# dosimeter.net
KiCad netlist of a schematic drawn in EAGLE
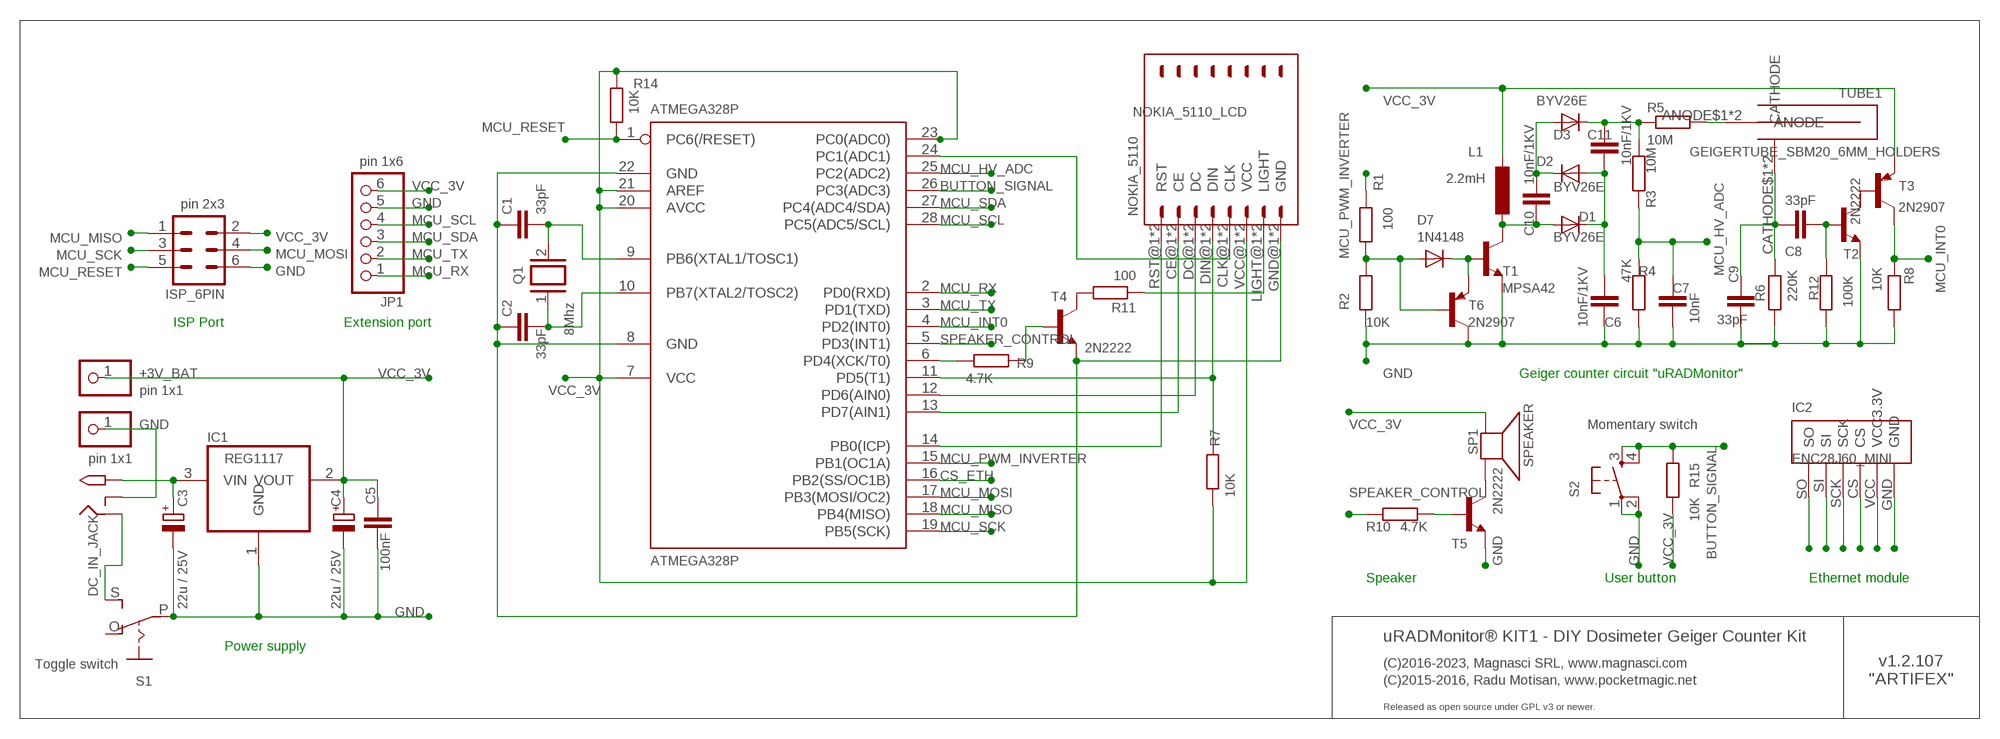
[diagram p0: schematic, sheet 1]

(export (version "E")
  (design (tool "Eeschema 10.0.6"))
  (components
    (comp (ref "+3V_BAT")
      (value "pin 1x1")
      (footprint "eagle-import:1X01")
      (libsource (lib "eagle-import") (part "PINHD-1X1"))
    )
    (comp (ref "ATMEGA328P")
      (value "ATMEGA328P")
      (footprint "eagle-import:DIL28-3")
      (libsource (lib "eagle-import") (part "MEGA8-P"))
    )
    (comp (ref "C1")
      (value "33pF")
      (footprint "eagle-import:C2.5-2")
      (libsource (lib "eagle-import") (part "C2.5/2"))
    )
    (comp (ref "C2")
      (value "33pF")
      (footprint "eagle-import:C2.5-2")
      (libsource (lib "eagle-import") (part "C2.5/2"))
    )
    (comp (ref "C3")
      (value "22u / 25V")
      (footprint "eagle-import:TT2D4L")
      (libsource (lib "eagle-import") (part "CPOL-EUTT2D4L"))
    )
    (comp (ref "C4")
      (value "22u / 25V")
      (footprint "eagle-import:TT2D4L")
      (libsource (lib "eagle-import") (part "CPOL-EUTT2D4L"))
    )
    (comp (ref "C5")
      (value "100nF")
      (footprint "eagle-import:C2.5-2")
      (libsource (lib "eagle-import") (part "C2.5/2"))
    )
    (comp (ref "C6")
      (value "10nF/1KV")
      (footprint "eagle-import:C5B3")
      (libsource (lib "eagle-import") (part "C5/3"))
    )
    (comp (ref "C7")
      (value "10nF")
      (footprint "eagle-import:C2.5-2")
      (libsource (lib "eagle-import") (part "C2.5/2"))
    )
    (comp (ref "C8")
      (value "33pF")
      (footprint "eagle-import:C2.5-2")
      (libsource (lib "eagle-import") (part "C2.5/2"))
    )
    (comp (ref "C9")
      (value "33pF")
      (footprint "eagle-import:C2.5-2")
      (libsource (lib "eagle-import") (part "C2.5/2"))
    )
    (comp (ref "C10")
      (value "10nF/1KV")
      (footprint "eagle-import:C5B3")
      (libsource (lib "eagle-import") (part "C5/3"))
    )
    (comp (ref "C11")
      (value "10nF/1KV")
      (footprint "eagle-import:C5B3")
      (libsource (lib "eagle-import") (part "C5/3"))
    )
    (comp (ref "D1")
      (value "BYV26E")
      (footprint "eagle-import:DO41-7.6")
      (libsource (lib "eagle-import") (part "DIODE-DO41-7.6"))
    )
    (comp (ref "D2")
      (value "BYV26E")
      (footprint "eagle-import:DO41-7.6")
      (libsource (lib "eagle-import") (part "DIODE-DO41-7.6"))
    )
    (comp (ref "D3")
      (value "BYV26E")
      (footprint "eagle-import:DO41-7.6")
      (libsource (lib "eagle-import") (part "DIODE-DO41-7.6"))
    )
    (comp (ref "D7")
      (value "1N4148")
      (footprint "eagle-import:D-5")
      (libsource (lib "eagle-import") (part "DIODE-D-5"))
    )
    (comp (ref "DC_IN_JACK")
      (value "DC IN JACK")
      (footprint "eagle-import:PJ-102A")
      (libsource (lib "eagle-import") (part "2.1MMJACKTHM"))
    )
    (comp (ref "GND")
      (value "pin 1x1")
      (footprint "eagle-import:1X01")
      (libsource (lib "eagle-import") (part "PINHD-1X1"))
    )
    (comp (ref "IC1")
      (value "REG1117")
      (footprint "eagle-import:SOT223")
      (libsource (lib "eagle-import") (part "REG1117"))
    )
    (comp (ref "IC2")
      (value "ENC28J60_MINI")
      (footprint "eagle-import:ENC28J60_MINI")
      (libsource (lib "eagle-import") (part "ENC28J60_MINI"))
    )
    (comp (ref "ISP_6PIN")
      (value "pin 2x3")
      (footprint "eagle-import:MA03-2")
      (libsource (lib "eagle-import") (part "MA03-2"))
    )
    (comp (ref "JP1")
      (value "pin 1x6")
      (footprint "eagle-import:1X06-CLEAN")
      (libsource (lib "eagle-import") (part "PINHD-1X6CLEAN"))
    )
    (comp (ref "L1")
      (value "2.2mH")
      (footprint "eagle-import:0207_10")
      (libsource (lib "eagle-import") (part "L-EU0207/10"))
    )
    (comp (ref "NOKIA_5110")
      (value "NOKIA_5110_LCD")
      (footprint "eagle-import:NOKIA5110")
      (libsource (lib "eagle-import") (part "NOKIA5110"))
    )
    (comp (ref "Q1")
      (value "8Mhz")
      (footprint "eagle-import:QS")
      (libsource (lib "eagle-import") (part "XTAL/S"))
    )
    (comp (ref "R1")
      (value "100")
      (footprint "eagle-import:0204_7")
      (libsource (lib "eagle-import") (part "R-EU_0204/7"))
    )
    (comp (ref "R2")
      (value "10K")
      (footprint "eagle-import:0204_7")
      (libsource (lib "eagle-import") (part "R-EU_0204/7"))
    )
    (comp (ref "R3")
      (value "10M")
      (footprint "eagle-import:0204_7")
      (libsource (lib "eagle-import") (part "R-EU_0204/7"))
    )
    (comp (ref "R4")
      (value "47K")
      (footprint "eagle-import:0204_7")
      (libsource (lib "eagle-import") (part "R-EU_0204/7"))
    )
    (comp (ref "R5")
      (value "10M")
      (footprint "eagle-import:0204_7")
      (libsource (lib "eagle-import") (part "R-EU_0204/7"))
    )
    (comp (ref "R6")
      (value "220K")
      (footprint "eagle-import:0204_7")
      (libsource (lib "eagle-import") (part "R-EU_0204/7"))
    )
    (comp (ref "R7")
      (value "10K")
      (footprint "eagle-import:0204_7")
      (libsource (lib "eagle-import") (part "R-EU_0204/7"))
    )
    (comp (ref "R8")
      (value "10K")
      (footprint "eagle-import:0204_7")
      (libsource (lib "eagle-import") (part "R-EU_0204/7"))
    )
    (comp (ref "R9")
      (value "4.7K")
      (footprint "eagle-import:0204_7")
      (libsource (lib "eagle-import") (part "R-EU_0204/7"))
    )
    (comp (ref "R10")
      (value "4.7K")
      (footprint "eagle-import:0204_7")
      (libsource (lib "eagle-import") (part "R-EU_0204/7"))
    )
    (comp (ref "R11")
      (value "100")
      (footprint "eagle-import:0204_7")
      (libsource (lib "eagle-import") (part "R-EU_0204/7"))
    )
    (comp (ref "R12")
      (value "100K")
      (footprint "eagle-import:0204_7")
      (libsource (lib "eagle-import") (part "R-EU_0204/7"))
    )
    (comp (ref "R14")
      (value "10K")
      (footprint "eagle-import:0204_7")
      (libsource (lib "eagle-import") (part "R-EU_0204/7"))
    )
    (comp (ref "R15")
      (value "10K")
      (footprint "eagle-import:0204_7")
      (libsource (lib "eagle-import") (part "R-EU_0204/7"))
    )
    (comp (ref "S1")
      (value "Toggle switch")
      (footprint "eagle-import:EG1218")
      (libsource (lib "eagle-import") (part "EG1218S"))
    )
    (comp (ref "S2")
      (value "Momentary switch")
      (footprint "eagle-import:TACTILE-PTH")
      (libsource (lib "eagle-import") (part "TAC_SWITCHPTH"))
    )
    (comp (ref "SP1")
      (value "SPEAKER")
      (footprint "eagle-import:AL60P")
      (libsource (lib "eagle-import") (part "SPEAKER/AL60P"))
    )
    (comp (ref "T1")
      (value "MPSA42")
      (footprint "eagle-import:TO92-EBC-OVAL")
      (libsource (lib "eagle-import") (part "2N2222"))
    )
    (comp (ref "T2")
      (value "2N2222")
      (footprint "eagle-import:TO92-EBC")
      (libsource (lib "eagle-import") (part "-NPN-TO92-EBC2N2222"))
    )
    (comp (ref "T3")
      (value "2N2907")
      (footprint "eagle-import:TO92-EBC-OVAL")
      (libsource (lib "eagle-import") (part "2N2907"))
    )
    (comp (ref "T4")
      (value "2N2222")
      (footprint "eagle-import:TO92-EBC")
      (libsource (lib "eagle-import") (part "-NPN-TO92-EBC2N2222"))
    )
    (comp (ref "T5")
      (value "2N2222")
      (footprint "eagle-import:TO92-EBC")
      (libsource (lib "eagle-import") (part "-NPN-TO92-EBC2N2222"))
    )
    (comp (ref "T6")
      (value "2N2907")
      (footprint "eagle-import:TO92-EBC-OVAL")
      (libsource (lib "eagle-import") (part "2N2907"))
    )
    (comp (ref "TUBE1")
      (value "GEIGERTUBE_SBM20_6MM_HOLDERS")
      (footprint "eagle-import:GEIGERTUBE_SBM20_6MM_HOLDERS")
      (libsource (lib "eagle-import") (part "GEIGERTUBE_SBM20_6MM_HOLDERS"))
    )
  )
  (nets
    (net (code "1") (name "BUTTON_SIGNAL") (class "Default")
      (node (ref "ATMEGA328P") (pin "26") (pinfunction "PC3(ADC3)_26") (pintype "bidirectional"))
      (node (ref "R15") (pin "1") (pinfunction "1_1") (pintype "passive"))
      (node (ref "S2") (pin "3") (pinfunction "3_3") (pintype "passive"))
      (node (ref "S2") (pin "4") (pinfunction "4_4") (pintype "passive"))
    )
    (net (code "2") (name "CS_ETH") (class "Default")
      (node (ref "ATMEGA328P") (pin "16") (pinfunction "PB2(SS/OC1B)_16") (pintype "bidirectional"))
      (node (ref "IC2") (pin "CS") (pinfunction "CS_CS") (pintype "bidirectional"))
    )
    (net (code "3") (name "GND") (class "Default")
      (node (ref "ATMEGA328P") (pin "22") (pinfunction "GND_22") (pintype "power_in"))
      (node (ref "ATMEGA328P") (pin "8") (pinfunction "GND_8") (pintype "power_in"))
      (node (ref "C1") (pin "1") (pinfunction "1_1") (pintype "passive"))
      (node (ref "C2") (pin "1") (pinfunction "1_1") (pintype "passive"))
      (node (ref "C3") (pin "-") (pinfunction "-_-") (pintype "passive"))
      (node (ref "C4") (pin "-") (pinfunction "-_-") (pintype "passive"))
      (node (ref "C5") (pin "1") (pinfunction "1_1") (pintype "passive"))
      (node (ref "C6") (pin "2") (pinfunction "2_2") (pintype "passive"))
      (node (ref "C7") (pin "1") (pinfunction "1_1") (pintype "passive"))
      (node (ref "C9") (pin "2") (pinfunction "2_2") (pintype "passive"))
      (node (ref "IC1") (pin "1") (pinfunction "GND_1") (pintype "power_in"))
      (node (ref "IC2") (pin "GND") (pinfunction "GND_GND") (pintype "bidirectional"))
      (node (ref "ISP_6PIN") (pin "6") (pinfunction "6_6") (pintype "passive"))
      (node (ref "JP1") (pin "5") (pinfunction "5_5") (pintype "passive"))
      (node (ref "NOKIA_5110") (pin "GND@1") (pinfunction "GND_GND@1") (pintype "bidirectional"))
      (node (ref "NOKIA_5110") (pin "GND@2") (pinfunction "GND_GND@2") (pintype "bidirectional"))
      (node (ref "R12") (pin "2") (pinfunction "2_2") (pintype "passive"))
      (node (ref "R2") (pin "1") (pinfunction "1_1") (pintype "passive"))
      (node (ref "R4") (pin "2") (pinfunction "2_2") (pintype "passive"))
      (node (ref "R6") (pin "1") (pinfunction "1_1") (pintype "passive"))
      (node (ref "R8") (pin "2") (pinfunction "2_2") (pintype "passive"))
      (node (ref "S1") (pin "P") (pinfunction "P_P") (pintype "passive"))
      (node (ref "S2") (pin "1") (pinfunction "1_1") (pintype "passive"))
      (node (ref "S2") (pin "2") (pinfunction "2_2") (pintype "passive"))
      (node (ref "T1") (pin "E") (pinfunction "E_E") (pintype "passive"))
      (node (ref "T2") (pin "E") (pinfunction "E_E") (pintype "passive"))
      (node (ref "T4") (pin "E") (pinfunction "E_E") (pintype "passive"))
      (node (ref "T5") (pin "E") (pinfunction "E_E") (pintype "passive"))
      (node (ref "T6") (pin "C") (pinfunction "C_C") (pintype "passive"))
    )
    (net (code "4") (name "MCU_HV_ADC") (class "Default")
      (node (ref "ATMEGA328P") (pin "25") (pinfunction "PC2(ADC2)_25") (pintype "bidirectional"))
      (node (ref "C7") (pin "2") (pinfunction "2_2") (pintype "passive"))
      (node (ref "R3") (pin "1") (pinfunction "1_1") (pintype "passive"))
      (node (ref "R4") (pin "1") (pinfunction "1_1") (pintype "passive"))
    )
    (net (code "5") (name "MCU_INT0") (class "Default")
      (node (ref "ATMEGA328P") (pin "4") (pinfunction "PD2(INT0)_4") (pintype "bidirectional"))
      (node (ref "R8") (pin "1") (pinfunction "1_1") (pintype "passive"))
      (node (ref "T3") (pin "C") (pinfunction "C_C") (pintype "passive"))
    )
    (net (code "6") (name "MCU_MISO") (class "Default")
      (node (ref "ATMEGA328P") (pin "18") (pinfunction "PB4(MISO)_18") (pintype "bidirectional"))
      (node (ref "IC2") (pin "SO") (pinfunction "SO_SO") (pintype "bidirectional"))
      (node (ref "ISP_6PIN") (pin "1") (pinfunction "1_1") (pintype "passive"))
    )
    (net (code "7") (name "MCU_MOSI") (class "Default")
      (node (ref "ATMEGA328P") (pin "17") (pinfunction "PB3(MOSI/OC2)_17") (pintype "bidirectional"))
      (node (ref "IC2") (pin "SI") (pinfunction "SI_SI") (pintype "bidirectional"))
      (node (ref "ISP_6PIN") (pin "4") (pinfunction "4_4") (pintype "passive"))
    )
    (net (code "8") (name "MCU_PWM_INVERTER") (class "Default")
      (node (ref "ATMEGA328P") (pin "15") (pinfunction "PB1(OC1A)_15") (pintype "bidirectional"))
      (node (ref "R1") (pin "1") (pinfunction "1_1") (pintype "passive"))
    )
    (net (code "9") (name "MCU_RESET") (class "Default")
      (node (ref "ATMEGA328P") (pin "1") (pinfunction "PC6(/RESET)_1") (pintype "bidirectional"))
      (node (ref "ISP_6PIN") (pin "5") (pinfunction "5_5") (pintype "passive"))
      (node (ref "R14") (pin "1") (pinfunction "1_1") (pintype "passive"))
    )
    (net (code "10") (name "MCU_RX") (class "Default")
      (node (ref "ATMEGA328P") (pin "2") (pinfunction "PD0(RXD)_2") (pintype "bidirectional"))
      (node (ref "JP1") (pin "1") (pinfunction "1_1") (pintype "passive"))
    )
    (net (code "11") (name "MCU_SCK") (class "Default")
      (node (ref "ATMEGA328P") (pin "19") (pinfunction "PB5(SCK)_19") (pintype "bidirectional"))
      (node (ref "IC2") (pin "SCK") (pinfunction "SCK_SCK") (pintype "bidirectional"))
      (node (ref "ISP_6PIN") (pin "3") (pinfunction "3_3") (pintype "passive"))
    )
    (net (code "12") (name "MCU_SCL") (class "Default")
      (node (ref "ATMEGA328P") (pin "28") (pinfunction "PC5(ADC5/SCL)_28") (pintype "bidirectional"))
      (node (ref "JP1") (pin "4") (pinfunction "4_4") (pintype "passive"))
    )
    (net (code "13") (name "MCU_SDA") (class "Default")
      (node (ref "ATMEGA328P") (pin "27") (pinfunction "PC4(ADC4/SDA)_27") (pintype "bidirectional"))
      (node (ref "JP1") (pin "3") (pinfunction "3_3") (pintype "passive"))
    )
    (net (code "14") (name "MCU_TX") (class "Default")
      (node (ref "ATMEGA328P") (pin "3") (pinfunction "PD1(TXD)_3") (pintype "bidirectional"))
      (node (ref "JP1") (pin "2") (pinfunction "2_2") (pintype "passive"))
    )
    (net (code "15") (name "N$27") (class "Default")
      (node (ref "D7") (pin "A") (pinfunction "A_A") (pintype "passive"))
      (node (ref "R1") (pin "2") (pinfunction "2_2") (pintype "passive"))
      (node (ref "R2") (pin "2") (pinfunction "2_2") (pintype "passive"))
      (node (ref "T6") (pin "B") (pinfunction "B_B") (pintype "passive"))
    )
    (net (code "16") (name "Net-(ATMEGA328P-PB0(ICP))") (class "Default")
      (node (ref "ATMEGA328P") (pin "14") (pinfunction "PB0(ICP)_14") (pintype "bidirectional"))
      (node (ref "NOKIA_5110") (pin "RST@1") (pinfunction "RST_RST@1") (pintype "bidirectional"))
      (node (ref "NOKIA_5110") (pin "RST@2") (pinfunction "RST_RST@2") (pintype "bidirectional"))
    )
    (net (code "17") (name "Net-(ATMEGA328P-PB6(XTAL1{slash}TOSC1))") (class "Default")
      (node (ref "ATMEGA328P") (pin "9") (pinfunction "PB6(XTAL1/TOSC1)_9") (pintype "bidirectional"))
      (node (ref "C1") (pin "2") (pinfunction "2_2") (pintype "passive"))
      (node (ref "Q1") (pin "2") (pinfunction "2_2") (pintype "passive"))
    )
    (net (code "18") (name "Net-(ATMEGA328P-PB7(XTAL2{slash}TOSC2))") (class "Default")
      (node (ref "ATMEGA328P") (pin "10") (pinfunction "PB7(XTAL2/TOSC2)_10") (pintype "bidirectional"))
      (node (ref "C2") (pin "2") (pinfunction "2_2") (pintype "passive"))
      (node (ref "Q1") (pin "1") (pinfunction "1_1") (pintype "passive"))
    )
    (net (code "19") (name "Net-(ATMEGA328P-PC1(ADC1))") (class "Default")
      (node (ref "ATMEGA328P") (pin "24") (pinfunction "PC1(ADC1)_24") (pintype "bidirectional"))
      (node (ref "NOKIA_5110") (pin "CLK@1") (pinfunction "CLK_CLK@1") (pintype "bidirectional"))
      (node (ref "NOKIA_5110") (pin "CLK@2") (pinfunction "CLK_CLK@2") (pintype "bidirectional"))
    )
    (net (code "20") (name "Net-(ATMEGA328P-PD4(XCK{slash}T0))") (class "Default")
      (node (ref "ATMEGA328P") (pin "6") (pinfunction "PD4(XCK/T0)_6") (pintype "bidirectional"))
      (node (ref "R9") (pin "1") (pinfunction "1_1") (pintype "passive"))
    )
    (net (code "21") (name "Net-(ATMEGA328P-PD5(T1))") (class "Default")
      (node (ref "ATMEGA328P") (pin "11") (pinfunction "PD5(T1)_11") (pintype "bidirectional"))
      (node (ref "NOKIA_5110") (pin "DIN@1") (pinfunction "DIN_DIN@1") (pintype "bidirectional"))
      (node (ref "NOKIA_5110") (pin "DIN@2") (pinfunction "DIN_DIN@2") (pintype "bidirectional"))
      (node (ref "R7") (pin "2") (pinfunction "2_2") (pintype "passive"))
    )
    (net (code "22") (name "Net-(ATMEGA328P-PD6(AIN0))") (class "Default")
      (node (ref "ATMEGA328P") (pin "12") (pinfunction "PD6(AIN0)_12") (pintype "bidirectional"))
      (node (ref "NOKIA_5110") (pin "DC@1") (pinfunction "DC_DC@1") (pintype "bidirectional"))
      (node (ref "NOKIA_5110") (pin "DC@2") (pinfunction "DC_DC@2") (pintype "bidirectional"))
    )
    (net (code "23") (name "Net-(ATMEGA328P-PD7(AIN1))") (class "Default")
      (node (ref "ATMEGA328P") (pin "13") (pinfunction "PD7(AIN1)_13") (pintype "bidirectional"))
      (node (ref "NOKIA_5110") (pin "CE@1") (pinfunction "CE_CE@1") (pintype "bidirectional"))
      (node (ref "NOKIA_5110") (pin "CE@2") (pinfunction "CE_CE@2") (pintype "bidirectional"))
    )
    (net (code "24") (name "Net-(C8-Pad1)") (class "Default")
      (node (ref "C8") (pin "1") (pinfunction "1_1") (pintype "passive"))
      (node (ref "R12") (pin "1") (pinfunction "1_1") (pintype "passive"))
      (node (ref "T2") (pin "B") (pinfunction "B_B") (pintype "passive"))
    )
    (net (code "25") (name "Net-(C8-Pad2)") (class "Default")
      (node (ref "C8") (pin "2") (pinfunction "2_2") (pintype "passive"))
      (node (ref "C9") (pin "1") (pinfunction "1_1") (pintype "passive"))
      (node (ref "R6") (pin "2") (pinfunction "2_2") (pintype "passive"))
      (node (ref "TUBE1") (pin "CATHODE$1") (pinfunction "CATHODE_CATHODE$1") (pintype "bidirectional"))
      (node (ref "TUBE1") (pin "CATHODE$2") (pinfunction "CATHODE_CATHODE$2") (pintype "bidirectional"))
    )
    (net (code "26") (name "Net-(C10-Pad1)") (class "Default")
      (node (ref "C10") (pin "1") (pinfunction "1_1") (pintype "passive"))
      (node (ref "D2") (pin "C") (pinfunction "C_C") (pintype "passive"))
      (node (ref "D3") (pin "A") (pinfunction "A_A") (pintype "passive"))
    )
    (net (code "27") (name "Net-(C10-Pad2)") (class "Default")
      (node (ref "C10") (pin "2") (pinfunction "2_2") (pintype "passive"))
      (node (ref "D1") (pin "A") (pinfunction "A_A") (pintype "passive"))
      (node (ref "L1") (pin "2") (pinfunction "2_2") (pintype "passive"))
      (node (ref "T1") (pin "C") (pinfunction "C_C") (pintype "passive"))
    )
    (net (code "28") (name "Net-(C11-Pad1)") (class "Default")
      (node (ref "C11") (pin "1") (pinfunction "1_1") (pintype "passive"))
      (node (ref "D3") (pin "C") (pinfunction "C_C") (pintype "passive"))
      (node (ref "R3") (pin "2") (pinfunction "2_2") (pintype "passive"))
      (node (ref "R5") (pin "1") (pinfunction "1_1") (pintype "passive"))
    )
    (net (code "29") (name "Net-(C11-Pad2)") (class "Default")
      (node (ref "C11") (pin "2") (pinfunction "2_2") (pintype "passive"))
      (node (ref "C6") (pin "1") (pinfunction "1_1") (pintype "passive"))
      (node (ref "D1") (pin "C") (pinfunction "C_C") (pintype "passive"))
      (node (ref "D2") (pin "A") (pinfunction "A_A") (pintype "passive"))
    )
    (net (code "30") (name "Net-(D7-PadC)") (class "Default")
      (node (ref "D7") (pin "C") (pinfunction "C_C") (pintype "passive"))
      (node (ref "T1") (pin "B") (pinfunction "B_B") (pintype "passive"))
      (node (ref "T6") (pin "E") (pinfunction "E_E") (pintype "passive"))
    )
    (net (code "31") (name "Net-(DC_IN_JACK-PadRING)") (class "Default")
      (node (ref "DC_IN_JACK") (pin "RING") (pinfunction "RING_RING") (pintype "bidirectional"))
      (node (ref "S1") (pin "S") (pinfunction "S_S") (pintype "passive"))
    )
    (net (code "32") (name "Net-(DC_IN_JACK-PadRING_SW)") (class "Default")
      (node (ref "DC_IN_JACK") (pin "RING_SW") (pinfunction "RING_SW_RING_SW") (pintype "bidirectional"))
      (node (ref "GND") (pin "1") (pinfunction "1_1") (pintype "passive"))
    )
    (net (code "33") (name "Net-(IC1-VIN)") (class "Default")
      (node (ref "C3") (pin "+") (pinfunction "+_+") (pintype "passive"))
      (node (ref "DC_IN_JACK") (pin "TIP") (pinfunction "TIP_TIP") (pintype "bidirectional"))
      (node (ref "IC1") (pin "3") (pinfunction "VIN_3") (pintype "input"))
    )
    (net (code "34") (name "Net-(NOKIA_5110-LIGHT-PadLIGHT@1)") (class "Default")
      (node (ref "NOKIA_5110") (pin "LIGHT@1") (pinfunction "LIGHT_LIGHT@1") (pintype "bidirectional"))
      (node (ref "NOKIA_5110") (pin "LIGHT@2") (pinfunction "LIGHT_LIGHT@2") (pintype "bidirectional"))
      (node (ref "R11") (pin "1") (pinfunction "1_1") (pintype "passive"))
    )
    (net (code "35") (name "Net-(R5-Pad2)") (class "Default")
      (node (ref "R5") (pin "2") (pinfunction "2_2") (pintype "passive"))
      (node (ref "TUBE1") (pin "ANODE$1") (pinfunction "ANODE_ANODE$1") (pintype "bidirectional"))
      (node (ref "TUBE1") (pin "ANODE$2") (pinfunction "ANODE_ANODE$2") (pintype "bidirectional"))
    )
    (net (code "36") (name "Net-(R9-Pad2)") (class "Default")
      (node (ref "R9") (pin "2") (pinfunction "2_2") (pintype "passive"))
      (node (ref "T4") (pin "B") (pinfunction "B_B") (pintype "passive"))
    )
    (net (code "37") (name "Net-(R10-Pad2)") (class "Default")
      (node (ref "R10") (pin "2") (pinfunction "2_2") (pintype "passive"))
      (node (ref "T5") (pin "B") (pinfunction "B_B") (pintype "passive"))
    )
    (net (code "38") (name "Net-(R11-Pad2)") (class "Default")
      (node (ref "R11") (pin "2") (pinfunction "2_2") (pintype "passive"))
      (node (ref "T4") (pin "C") (pinfunction "C_C") (pintype "passive"))
    )
    (net (code "39") (name "Net-(SP1--)") (class "Default")
      (node (ref "SP1") (pin "2") (pinfunction "-_2") (pintype "passive"))
      (node (ref "T5") (pin "C") (pinfunction "C_C") (pintype "passive"))
    )
    (net (code "40") (name "Net-(T2-PadC)") (class "Default")
      (node (ref "T2") (pin "C") (pinfunction "C_C") (pintype "passive"))
      (node (ref "T3") (pin "B") (pinfunction "B_B") (pintype "passive"))
    )
    (net (code "41") (name "SPEAKER_CONTROL") (class "Default")
      (node (ref "ATMEGA328P") (pin "5") (pinfunction "PD3(INT1)_5") (pintype "bidirectional"))
      (node (ref "R10") (pin "1") (pinfunction "1_1") (pintype "passive"))
    )
    (net (code "42") (name "VCC_3V") (class "Default")
      (node (ref "+3V_BAT") (pin "1") (pinfunction "1_1") (pintype "passive"))
      (node (ref "ATMEGA328P") (pin "20") (pinfunction "AVCC_20") (pintype "power_in"))
      (node (ref "ATMEGA328P") (pin "21") (pinfunction "AREF_21") (pintype "passive"))
      (node (ref "ATMEGA328P") (pin "23") (pinfunction "PC0(ADC0)_23") (pintype "bidirectional"))
      (node (ref "ATMEGA328P") (pin "7") (pinfunction "VCC_7") (pintype "power_in"))
      (node (ref "C4") (pin "+") (pinfunction "+_+") (pintype "passive"))
      (node (ref "C5") (pin "2") (pinfunction "2_2") (pintype "passive"))
      (node (ref "IC1") (pin "2") (pinfunction "VOUT_2") (pintype "output"))
      (node (ref "IC2") (pin "VCC") (pinfunction "VCC3.3V_VCC") (pintype "bidirectional"))
      (node (ref "ISP_6PIN") (pin "2") (pinfunction "2_2") (pintype "passive"))
      (node (ref "JP1") (pin "6") (pinfunction "6_6") (pintype "passive"))
      (node (ref "L1") (pin "1") (pinfunction "1_1") (pintype "passive"))
      (node (ref "NOKIA_5110") (pin "VCC@1") (pinfunction "VCC_VCC@1") (pintype "bidirectional"))
      (node (ref "NOKIA_5110") (pin "VCC@2") (pinfunction "VCC_VCC@2") (pintype "bidirectional"))
      (node (ref "R14") (pin "2") (pinfunction "2_2") (pintype "passive"))
      (node (ref "R15") (pin "2") (pinfunction "2_2") (pintype "passive"))
      (node (ref "R7") (pin "1") (pinfunction "1_1") (pintype "passive"))
      (node (ref "SP1") (pin "1") (pinfunction "+_1") (pintype "passive"))
      (node (ref "T3") (pin "E") (pinfunction "E_E") (pintype "passive"))
    )
    (net (code "43") (name "unconnected-(S1-PadO)") (class "Default")
      (node (ref "S1") (pin "O") (pinfunction "O_O") (pintype "passive"))
    )
  )
)
